# connectors.net
KiCad netlist of a schematic drawn in Altium Designer
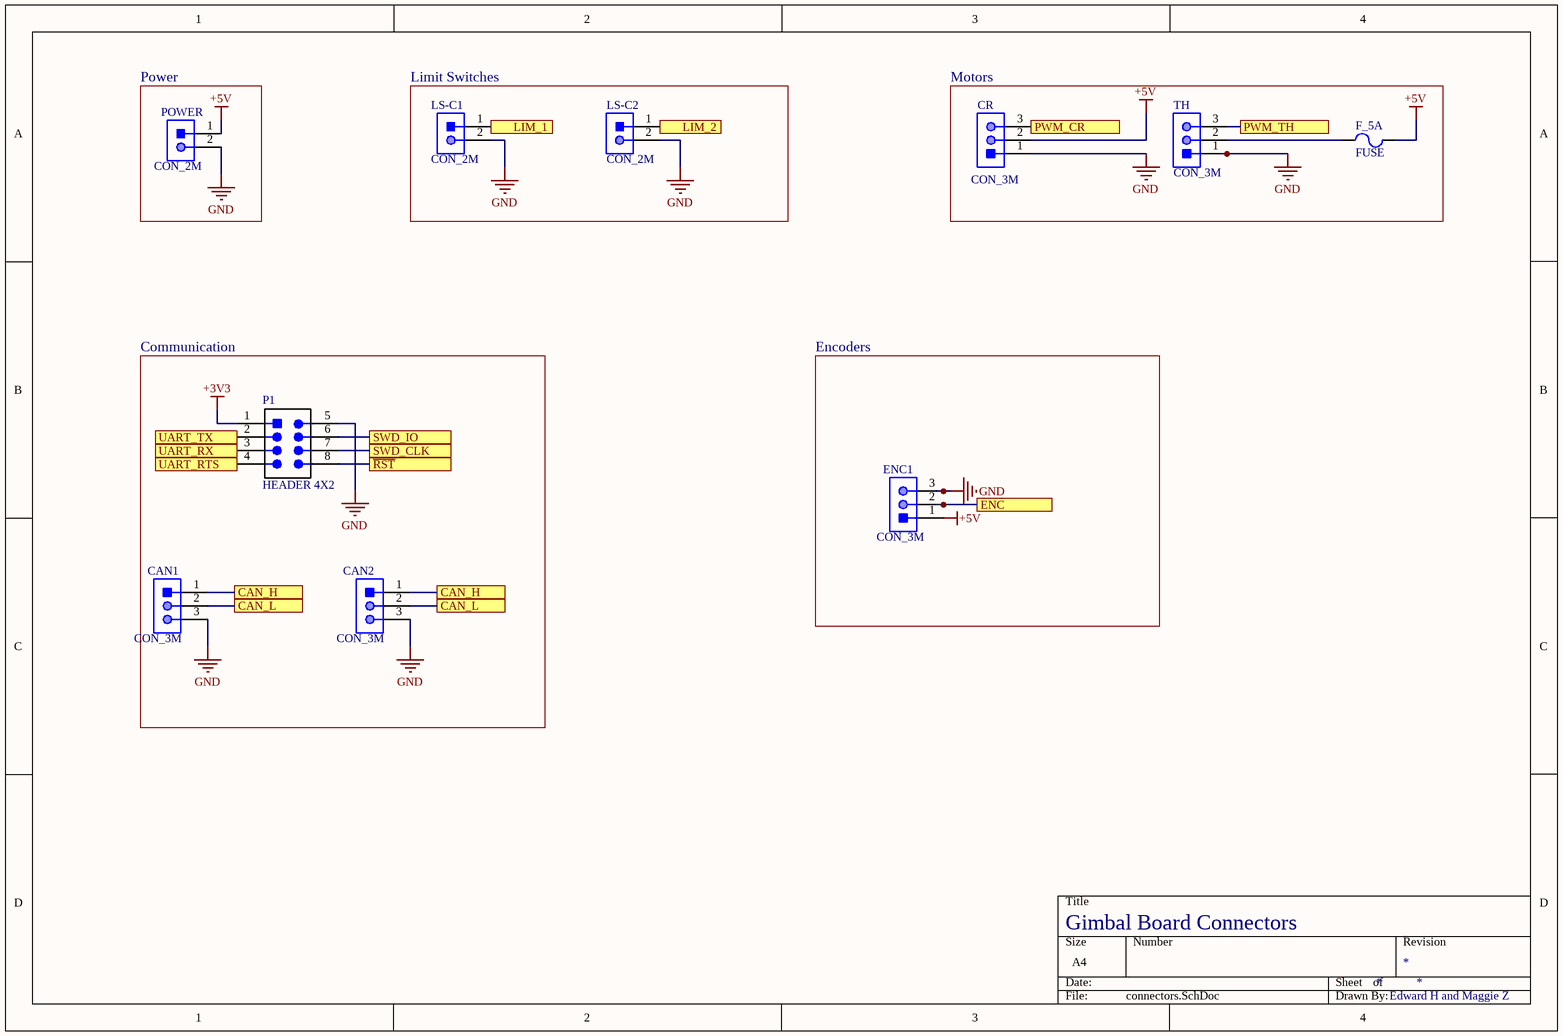
[diagram p0: connectors.SchDoc]

(export (version "E")
  (design (tool "Eeschema 10.0.6"))
  (components
    (comp (ref "CAN1") (value "CON_3M") (footprint "JST-B3B-SM4-TB") (libsource (lib "") (part "CON_3M_1")))
    (comp (ref "CAN2") (value "CON_3M") (footprint "JST-B3B-SM4-TB") (libsource (lib "") (part "CON_3M_1")))
    (comp (ref "CR")
      (value "CON_3M")
      (footprint "JST-B3B-SM4-TB")
      (libsource (lib "UWRT_Schematic_Library_2019") (part "CON_3M"))
    )
    (comp (ref "ENC1")
      (value "CON_3M")
      (footprint "JST-B3B-SM4-TB")
      (libsource (lib "UWRT_Schematic_Library_2019") (part "CON_3M"))
    )
    (comp (ref "F_5A")
      (value "FUSE")
      (footprint "FUSE")
      (description "FUSE HOLDER RADIAL 250V 6.3A PCB")
      (libsource (lib "UWRT_Schematic_Library_2019") (part "FUSE-5A"))
    )
    (comp (ref "LS-C1")
      (value "CON_2M")
      (footprint "JST-B2B-PHSK")
      (libsource (lib "UWRT_Schematic_Library_2019") (part "CON_2M"))
    )
    (comp (ref "LS-C2")
      (value "CON_2M")
      (footprint "JST-B2B-PHSK")
      (libsource (lib "UWRT_Schematic_Library_2019") (part "CON_2M"))
    )
    (comp (ref "P1")
      (value "HEADER 4X2")
      (footprint "UWRT_Footprint_Library_2019:HEADER_2X4")
      (description "Header, 4-Pin Dual row")
      (fields (field (name "MPN") "GRPB042VWVN-RC") (field (name "DIGIKEY PART NUMBER") "S9015E-04-ND"))
      (libsource (lib "UWRT_Schematic_Library_2019") (part "HEADER 4X2"))
    )
    (comp (ref "POWER")
      (value "CON_2M")
      (footprint "JST-B2B-PHSK")
      (libsource (lib "UWRT_Schematic_Library_2019") (part "CON_2M"))
    )
    (comp (ref "TH")
      (value "CON_3M")
      (footprint "JST B03B-PASK")
      (libsource (lib "UWRT_Schematic_Library_2019") (part "CON_3M"))
    )
  )
  (nets
    (net (code "1") (name "+3V3") (class "Default")
      (node (ref "P1") (pin "1") (pinfunction "VCC_1") (pintype "passive"))
    )
    (net (code "2") (name "+5V") (class "Default")
      (node (ref "CR") (pin "2") (pinfunction "2_2") (pintype "passive"))
      (node (ref "ENC1") (pin "1") (pinfunction "1_1") (pintype "passive"))
      (node (ref "F_5A") (pin "2") (pinfunction "2_2") (pintype "passive"))
      (node (ref "POWER") (pin "1") (pinfunction "1_1") (pintype "passive"))
    )
    (net (code "3") (name "/CAN_H") (class "Default")
      (node (ref "CAN1") (pin "1") (pinfunction "1_1") (pintype "passive"))
      (node (ref "CAN2") (pin "1") (pinfunction "1_1") (pintype "passive"))
    )
    (net (code "4") (name "/CAN_L") (class "Default")
      (node (ref "CAN1") (pin "2") (pinfunction "2_2") (pintype "passive"))
      (node (ref "CAN2") (pin "2") (pinfunction "2_2") (pintype "passive"))
    )
    (net (code "5") (name "/ENC") (class "Default")
      (node (ref "ENC1") (pin "2") (pinfunction "2_2") (pintype "passive"))
    )
    (net (code "6") (name "/LIM_1") (class "Default")
      (node (ref "LS-C1") (pin "1") (pinfunction "1_1") (pintype "passive"))
    )
    (net (code "7") (name "/LIM_2") (class "Default")
      (node (ref "LS-C2") (pin "1") (pinfunction "1_1") (pintype "passive"))
    )
    (net (code "8") (name "/PWM_CR") (class "Default")
      (node (ref "CR") (pin "3") (pinfunction "3_3") (pintype "passive"))
    )
    (net (code "9") (name "/PWM_TH") (class "Default")
      (node (ref "TH") (pin "3") (pinfunction "3_3") (pintype "passive"))
    )
    (net (code "10") (name "/SWD_CLK") (class "Default")
      (node (ref "P1") (pin "7") (pinfunction "3_7") (pintype "passive"))
    )
    (net (code "11") (name "/SWD_IO") (class "Default")
      (node (ref "P1") (pin "6") (pinfunction "2_6") (pintype "passive"))
    )
    (net (code "12") (name "/UART_RTS") (class "Default")
      (node (ref "P1") (pin "4") (pinfunction "4_4") (pintype "passive"))
    )
    (net (code "13") (name "/UART_RX") (class "Default")
      (node (ref "P1") (pin "3") (pinfunction "3_3") (pintype "passive"))
    )
    (net (code "14") (name "/UART_TX") (class "Default")
      (node (ref "P1") (pin "2") (pinfunction "2_2") (pintype "passive"))
    )
    (net (code "15") (name "/~{RST}") (class "Default")
      (node (ref "P1") (pin "8") (pinfunction "4_8") (pintype "passive"))
    )
    (net (code "16") (name "GND") (class "Default")
      (node (ref "CAN1") (pin "3") (pinfunction "3_3") (pintype "passive"))
      (node (ref "CAN2") (pin "3") (pinfunction "3_3") (pintype "passive"))
      (node (ref "CR") (pin "1") (pinfunction "1_1") (pintype "passive"))
      (node (ref "ENC1") (pin "3") (pinfunction "3_3") (pintype "passive"))
      (node (ref "LS-C1") (pin "2") (pinfunction "2_2") (pintype "passive"))
      (node (ref "LS-C2") (pin "2") (pinfunction "2_2") (pintype "passive"))
      (node (ref "P1") (pin "5") (pinfunction "GND_5") (pintype "passive"))
      (node (ref "POWER") (pin "2") (pinfunction "2_2") (pintype "passive"))
      (node (ref "TH") (pin "1") (pinfunction "1_1") (pintype "passive"))
    )
    (net (code "17") (name "Net-(F_5A-Pad1)") (class "Default")
      (node (ref "F_5A") (pin "1") (pinfunction "1_1") (pintype "passive"))
      (node (ref "TH") (pin "2") (pinfunction "2_2") (pintype "passive"))
    )
  )
)
